# Flash.net
KiCad netlist of a schematic drawn in Altium Designer
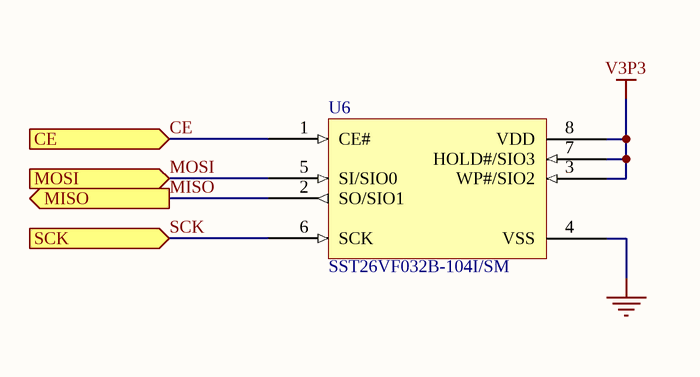
[diagram p0: Flash.SchDoc]

(export (version "E")
  (design (tool "Eeschema 10.0.6"))
  (components
    (comp (ref "U6")
      (value "SST26VF032B-104I/SM")
      (footprint "SOIC 8")
      (libsource (lib "Card_reader") (part "SST26VF032B-104I/SM"))
    )
  )
  (nets
    (net (code "1") (name "/CE") (class "Default")
      (node (ref "U6") (pin "1") (pinfunction "CE#_1") (pintype "input"))
    )
    (net (code "2") (name "/MISO") (class "Default")
      (node (ref "U6") (pin "2") (pinfunction "SO/SIO1_2") (pintype "output"))
    )
    (net (code "3") (name "/MOSI") (class "Default")
      (node (ref "U6") (pin "5") (pinfunction "SI/SIO0_5") (pintype "input"))
    )
    (net (code "4") (name "/SCK") (class "Default")
      (node (ref "U6") (pin "6") (pinfunction "SCK_6") (pintype "input"))
    )
    (net (code "5") (name "GND") (class "Default")
      (node (ref "U6") (pin "4") (pinfunction "VSS_4") (pintype "power_in"))
    )
    (net (code "6") (name "V3P3") (class "Default")
      (node (ref "U6") (pin "3") (pinfunction "WP#/SIO2_3") (pintype "input"))
      (node (ref "U6") (pin "7") (pinfunction "HOLD#/SIO3_7") (pintype "input"))
      (node (ref "U6") (pin "8") (pinfunction "VDD_8") (pintype "power_in"))
    )
  )
)
